# ledboard_noISP.net
KiCad netlist of a schematic drawn in EAGLE
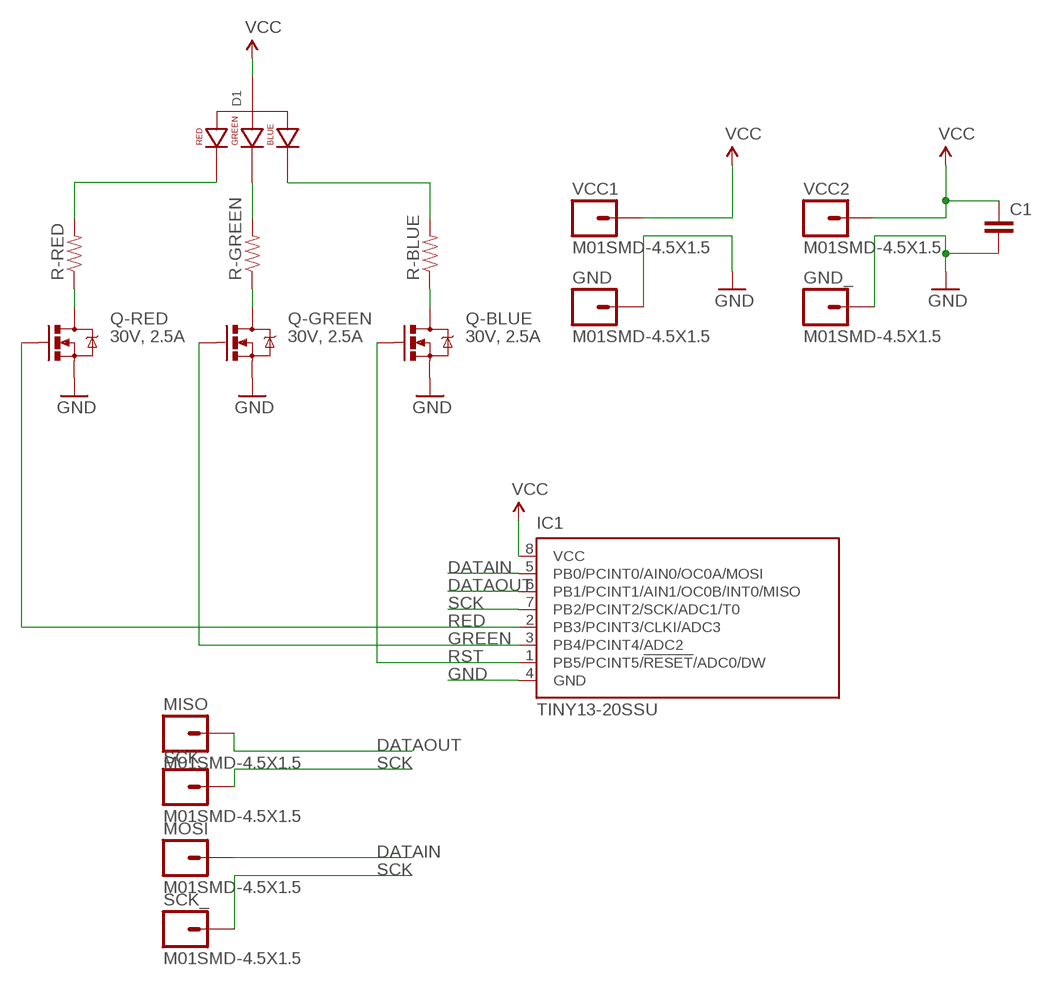
[diagram p0: schematic, sheet 1]

(export (version "E")
  (design (tool "Eeschema 10.0.6"))
  (components
    (comp (ref "C1")
      (value "CAP0805")
      (footprint "eagle-import:0805")
      (libsource (lib "eagle-import") (part "CAP0805"))
    )
    (comp (ref "D1")
      (value "LED-RGB-CA-THRUCLEAR")
      (footprint "eagle-import:LED-RGB-THRU")
      (libsource (lib "eagle-import") (part "LED-RGB-CA-THRUCLEAR"))
    )
    (comp (ref "GND")
      (value "M01SMD-4.5X1.5")
      (footprint "eagle-import:PAD-1.5X4.5")
      (libsource (lib "eagle-import") (part "M01SMD-4.5X1.5"))
    )
    (comp (ref "GND_")
      (value "M01SMD-4.5X1.5")
      (footprint "eagle-import:PAD-1.5X4.5")
      (libsource (lib "eagle-import") (part "M01SMD-4.5X1.5"))
    )
    (comp (ref "IC1")
      (value "TINY13-20SSU")
      (footprint "eagle-import:8S1")
      (fields (field (name "MPN") "ATTINY13-20SSU"))
      (libsource (lib "eagle-import") (part "TINY13SSU-20"))
    )
    (comp (ref "MISO")
      (value "M01SMD-4.5X1.5")
      (footprint "eagle-import:PAD-1.5X4.5")
      (libsource (lib "eagle-import") (part "M01SMD-4.5X1.5"))
    )
    (comp (ref "MOSI")
      (value "M01SMD-4.5X1.5")
      (footprint "eagle-import:PAD-1.5X4.5")
      (libsource (lib "eagle-import") (part "M01SMD-4.5X1.5"))
    )
    (comp (ref "Q-BLUE")
      (value "30V, 2.5A")
      (footprint "eagle-import:SOT23")
      (libsource (lib "eagle-import") (part "MOSFET-NCHANNELBSS123LT1G"))
    )
    (comp (ref "Q-GREEN")
      (value "30V, 2.5A")
      (footprint "eagle-import:SOT23")
      (libsource (lib "eagle-import") (part "MOSFET-NCHANNELBSS123LT1G"))
    )
    (comp (ref "Q-RED")
      (value "30V, 2.5A")
      (footprint "eagle-import:SOT23")
      (libsource (lib "eagle-import") (part "MOSFET-NCHANNELBSS123LT1G"))
    )
    (comp (ref "R-BLUE")
      (value "RESISTOR0603")
      (footprint "eagle-import:0603-RES")
      (libsource (lib "eagle-import") (part "RESISTOR0603"))
    )
    (comp (ref "R-GREEN")
      (value "RESISTOR0603")
      (footprint "eagle-import:0603-RES")
      (libsource (lib "eagle-import") (part "RESISTOR0603"))
    )
    (comp (ref "R-RED")
      (value "RESISTOR0603")
      (footprint "eagle-import:0603-RES")
      (libsource (lib "eagle-import") (part "RESISTOR0603"))
    )
    (comp (ref "SCK")
      (value "M01SMD-4.5X1.5")
      (footprint "eagle-import:PAD-1.5X4.5")
      (libsource (lib "eagle-import") (part "M01SMD-4.5X1.5"))
    )
    (comp (ref "SCK_")
      (value "M01SMD-4.5X1.5")
      (footprint "eagle-import:PAD-1.5X4.5")
      (libsource (lib "eagle-import") (part "M01SMD-4.5X1.5"))
    )
    (comp (ref "VCC1")
      (value "M01SMD-4.5X1.5")
      (footprint "eagle-import:PAD-1.5X4.5")
      (libsource (lib "eagle-import") (part "M01SMD-4.5X1.5"))
    )
    (comp (ref "VCC2")
      (value "M01SMD-4.5X1.5")
      (footprint "eagle-import:PAD-1.5X4.5")
      (libsource (lib "eagle-import") (part "M01SMD-4.5X1.5"))
    )
  )
  (nets
    (net (code "1") (name "/DATAIN") (class "Default")
      (node (ref "IC1") (pin "5") (pinfunction "PB0/PCINT0/AIN0/OC0A/MOSI_5") (pintype "bidirectional"))
      (node (ref "MOSI") (pin "P$1") (pinfunction "1_P$1") (pintype "passive"))
    )
    (net (code "2") (name "/DATAOUT") (class "Default")
      (node (ref "IC1") (pin "6") (pinfunction "PB1/PCINT1/AIN1/OC0B/INT0/MISO_6") (pintype "bidirectional"))
      (node (ref "MISO") (pin "P$1") (pinfunction "1_P$1") (pintype "passive"))
    )
    (net (code "3") (name "/GREEN") (class "Default")
      (node (ref "IC1") (pin "3") (pinfunction "PB4/PCINT4/ADC2_3") (pintype "bidirectional"))
      (node (ref "Q-GREEN") (pin "1") (pinfunction "G_1") (pintype "passive"))
    )
    (net (code "4") (name "/RED") (class "Default")
      (node (ref "IC1") (pin "2") (pinfunction "PB3/PCINT3/CLKI/ADC3_2") (pintype "bidirectional"))
      (node (ref "Q-RED") (pin "1") (pinfunction "G_1") (pintype "passive"))
    )
    (net (code "5") (name "/RST") (class "Default")
      (node (ref "IC1") (pin "1") (pinfunction "PB5/PCINT5/~{RESET}/ADC0/DW_1") (pintype "bidirectional"))
      (node (ref "Q-BLUE") (pin "1") (pinfunction "G_1") (pintype "passive"))
    )
    (net (code "6") (name "/SCK") (class "Default")
      (node (ref "IC1") (pin "7") (pinfunction "PB2/PCINT2/SCK/ADC1/T0_7") (pintype "bidirectional"))
      (node (ref "SCK") (pin "P$1") (pinfunction "1_P$1") (pintype "passive"))
      (node (ref "SCK_") (pin "P$1") (pinfunction "1_P$1") (pintype "passive"))
    )
    (net (code "7") (name "GND") (class "Default")
      (node (ref "C1") (pin "2") (pinfunction "2_2") (pintype "passive"))
      (node (ref "GND") (pin "P$1") (pinfunction "1_P$1") (pintype "passive"))
      (node (ref "GND_") (pin "P$1") (pinfunction "1_P$1") (pintype "passive"))
      (node (ref "IC1") (pin "4") (pinfunction "GND_4") (pintype "power_in"))
      (node (ref "Q-BLUE") (pin "2") (pinfunction "S_2") (pintype "passive"))
      (node (ref "Q-GREEN") (pin "2") (pinfunction "S_2") (pintype "passive"))
      (node (ref "Q-RED") (pin "2") (pinfunction "S_2") (pintype "passive"))
    )
    (net (code "8") (name "Net-(D1-BLUE_CATHODE)") (class "Default")
      (node (ref "D1") (pin "4") (pinfunction "BLUE_CATHODE_4") (pintype "bidirectional"))
      (node (ref "R-BLUE") (pin "2") (pinfunction "2_2") (pintype "passive"))
    )
    (net (code "9") (name "Net-(D1-GREEN_CATHODE)") (class "Default")
      (node (ref "D1") (pin "3") (pinfunction "GREEN_CATHODE_3") (pintype "bidirectional"))
      (node (ref "R-GREEN") (pin "2") (pinfunction "2_2") (pintype "passive"))
    )
    (net (code "10") (name "Net-(D1-RED_CATHODE)") (class "Default")
      (node (ref "D1") (pin "1") (pinfunction "RED_CATHODE_1") (pintype "bidirectional"))
      (node (ref "R-RED") (pin "2") (pinfunction "2_2") (pintype "passive"))
    )
    (net (code "11") (name "Net-(Q-BLUE-D)") (class "Default")
      (node (ref "Q-BLUE") (pin "3") (pinfunction "D_3") (pintype "passive"))
      (node (ref "R-BLUE") (pin "1") (pinfunction "1_1") (pintype "passive"))
    )
    (net (code "12") (name "Net-(Q-GREEN-D)") (class "Default")
      (node (ref "Q-GREEN") (pin "3") (pinfunction "D_3") (pintype "passive"))
      (node (ref "R-GREEN") (pin "1") (pinfunction "1_1") (pintype "passive"))
    )
    (net (code "13") (name "Net-(Q-RED-D)") (class "Default")
      (node (ref "Q-RED") (pin "3") (pinfunction "D_3") (pintype "passive"))
      (node (ref "R-RED") (pin "1") (pinfunction "1_1") (pintype "passive"))
    )
    (net (code "14") (name "VCC") (class "Default")
      (node (ref "C1") (pin "1") (pinfunction "1_1") (pintype "passive"))
      (node (ref "D1") (pin "2") (pinfunction "ANODE_2") (pintype "bidirectional"))
      (node (ref "IC1") (pin "8") (pinfunction "VCC_8") (pintype "power_in"))
      (node (ref "VCC1") (pin "P$1") (pinfunction "1_P$1") (pintype "passive"))
      (node (ref "VCC2") (pin "P$1") (pinfunction "1_P$1") (pintype "passive"))
    )
  )
)
